# main.net
KiCad netlist of a schematic drawn in Altium Designer
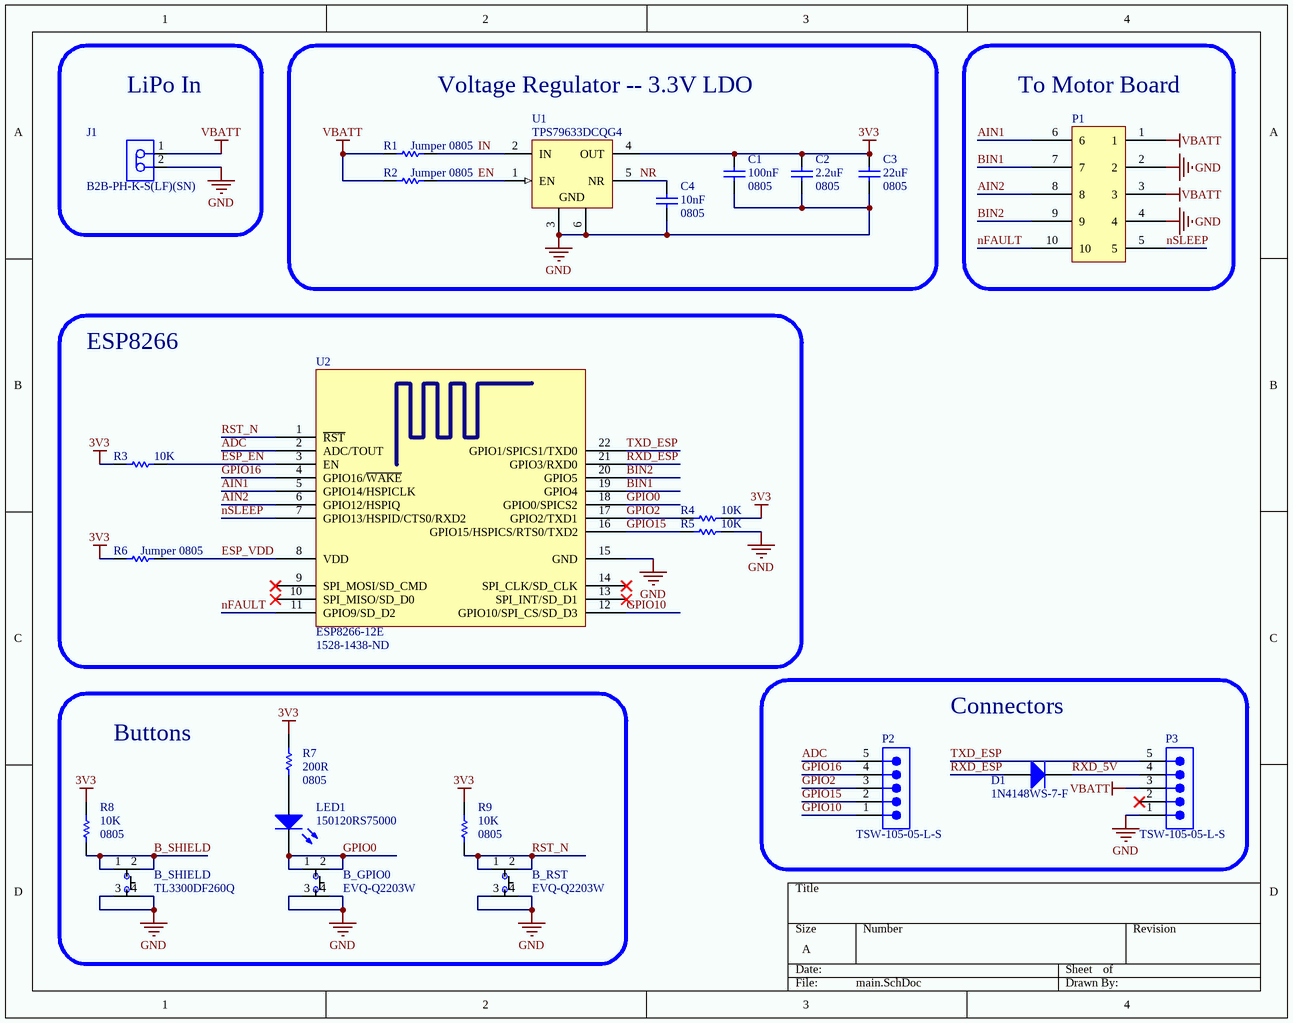
[diagram p0: main.SchDoc]

(export (version "E")
  (design (tool "Eeschema 10.0.6"))
  (components
    (comp (ref "B_GPIO0")
      (value "EVQ-Q2203W")
      (footprint "EVQ-Q2203W")
      (description "SWITCH TACTILE SPST-NO 0.02A 15V")
      (fields (field (name "MANUFACTURER") "Panasonic Electronic Components"))
      (libsource (lib "ESE292-2017F-Teaching-Staff") (part "EVQ-Q2203W"))
    )
    (comp (ref "B_RST")
      (value "EVQ-Q2203W")
      (footprint "EVQ-Q2203W")
      (description "SWITCH TACTILE SPST-NO 0.02A 15V")
      (fields (field (name "MANUFACTURER") "Panasonic Electronic Components"))
      (libsource (lib "ESE292-2017F-Teaching-Staff") (part "EVQ-Q2203W"))
    )
    (comp (ref "B_SHIELD")
      (value "TL3300DF260Q")
      (footprint "TL3300DF260Q")
      (description "SWITCH TACTILE SPST-NO 0.05A 12V")
      (fields (field (name "MANUFACTURER") "E-Switch"))
      (libsource (lib "ESE292-2017F-Teaching-Staff") (part "TL3300DF260Q"))
    )
    (comp (ref "C1")
      (value "100nF")
      (footprint "CAPC0805(2012)100_M")
      (description "CAP 100nF 10V ±20% 0805 (2012 Metric) Thickness 1mm SMD")
      (fields (field (name "TOLERANCE") "Â±20%") (field (name "CASE-EIA") "0805"))
      (libsource (lib "Altium Content Vault") (part "CMP-1036-04396-1"))
    )
    (comp (ref "C2")
      (value "2.2uF")
      (footprint "CAPC0805(2012)145_L")
      (description "CAP 2.2uF 10V ±20% 0805 (2012 Metric) Thickness 1.45mm SMD")
      (fields (field (name "CASE-EIA") "0805") (field (name "TOLERANCE") "Â±20%"))
      (libsource (lib "Altium Content Vault") (part "CMP-1036-04826-1"))
    )
    (comp (ref "C3")
      (value "22uF")
      (footprint "CAPC0805(2012)145_L")
      (description "CAP 22uF 10V ±10% 0805 (2012 Metric) Thickness 1.45mm SMD")
      (fields (field (name "CASE-EIA") "0805") (field (name "TOLERANCE") "Â±10%"))
      (libsource (lib "Altium Content Vault") (part "CMP-1036-04942-1"))
    )
    (comp (ref "C4")
      (value "10nF")
      (footprint "CAPC0805(2012)145_M")
      (description "CAP 10nF 10V ±10% 0805 (2012 Metric) Thickness 1.45mm SMD")
      (fields (field (name "CASE-EIA") "0805") (field (name "TOLERANCE") "Â±10%"))
      (libsource (lib "Altium Content Vault") (part "CMP-1036-03808-1"))
    )
    (comp (ref "D1")
      (value "1N4148WS-7-F")
      (footprint "DIOD-SOD323-2-A_V")
      (description "Fast Switching Diode, 75 V, 0.3 A, -65 to 150 degC, 2-Pin SOD323, RoHS, Tape and Reel")
      (libsource (lib "Altium Content Vault") (part "D-AK-2"))
    )
    (comp (ref "J1")
      (value "B2B-PH-K-S(LF)(SN)")
      (footprint "JST-B2B-PH-K-S_V")
      (fields (field (name "MANUFACTURER") "JST"))
      (libsource (lib "Altium Content Vault") (part "CN-2P-F-QF2"))
    )
    (comp (ref "LED1")
      (value "150120RS75000")
      (footprint "1206_A")
      (description "SMD mono-color Chip LED, WL-SMCW, Red")
      (fields (field (name "MANUFACTURER") "Wuerth Elektronik"))
      (libsource (lib "Altium Content Vault") (part "WE-LED_K1A2-2"))
    )
    (comp (ref "P1")
      (value "302-S101")
      (footprint "302-S101")
      (description "10 Positions Header, Shrouded Connector 0.100\" (2.54mm) Through Hole Gold")
      (fields (field (name "MANUFACTURER") "On-Shore Technology"))
      (libsource (lib "ESE292-2017F-Teaching-Staff") (part "302-S101"))
    )
    (comp (ref "P2")
      (value "TSW-105-05-L-S")
      (footprint "SMTC-TSW-105-05-X-S")
      (fields (field (name "MANUFACTURER") "Samtec"))
      (libsource (lib "Altium Content Vault") (part "SMTC-TSW-105-05-X-S"))
    )
    (comp (ref "P3")
      (value "TSW-105-05-L-S")
      (footprint "SMTC-TSW-105-05-X-S")
      (fields (field (name "MANUFACTURER") "Samtec"))
      (libsource (lib "Altium Content Vault") (part "SMTC-TSW-105-05-X-S"))
    )
    (comp (ref "R1")
      (value "Jumper 0805")
      (footprint "RESC0805(2012)_N")
      (description "Jumper 0805 (2012 Metric)")
      (fields (field (name "TOLERANCE") "None"))
      (libsource (lib "Altium Content Vault") (part "RES"))
    )
    (comp (ref "R2")
      (value "Jumper 0805")
      (footprint "RESC0805(2012)_N")
      (description "Jumper 0805 (2012 Metric)")
      (fields (field (name "TOLERANCE") "None"))
      (libsource (lib "Altium Content Vault") (part "RES"))
    )
    (comp (ref "R3")
      (value "10K")
      (footprint "RESC0805(2012)_L")
      (description "10K 0.125W 5% 0805 (2012 Metric)  SMD")
      (fields (field (name "POWER") "0.125 W") (field (name "TOLERANCE") "5 %"))
      (libsource (lib "Altium Content Vault") (part "CMP-1013-00098-1"))
    )
    (comp (ref "R4")
      (value "10K")
      (footprint "RESC0805(2012)_L")
      (description "10K 0.125W 5% 0805 (2012 Metric)  SMD")
      (fields (field (name "POWER") "0.125 W") (field (name "TOLERANCE") "5 %"))
      (libsource (lib "Altium Content Vault") (part "CMP-1013-00098-1"))
    )
    (comp (ref "R5")
      (value "10K")
      (footprint "RESC0805(2012)_L")
      (description "10K 0.125W 5% 0805 (2012 Metric)  SMD")
      (fields (field (name "POWER") "0.125 W") (field (name "TOLERANCE") "5 %"))
      (libsource (lib "Altium Content Vault") (part "CMP-1013-00098-1"))
    )
    (comp (ref "R6")
      (value "Jumper 0805")
      (footprint "RESC0805(2012)_N")
      (description "Jumper 0805 (2012 Metric)")
      (fields (field (name "TOLERANCE") "None"))
      (libsource (lib "Altium Content Vault") (part "RES"))
    )
    (comp (ref "R7")
      (value "200R")
      (footprint "RESC0805(2012)_N")
      (description "200R 0.125W 5% 0805 (2012 Metric)  SMD")
      (fields
        (field (name "TOLERANCE") "5 %")
        (field (name "CASE-EIA") "0805")
        (field (name "POWER") "0.125 W")
      )
      (libsource (lib "Altium Content Vault") (part "CMP-1013-00057-1"))
    )
    (comp (ref "R8")
      (value "10K")
      (footprint "RESC0805(2012)_L")
      (description "10K 0.125W 5% 0805 (2012 Metric)  SMD")
      (fields
        (field (name "CASE-EIA") "0805")
        (field (name "POWER") "0.125 W")
        (field (name "TOLERANCE") "5 %")
      )
      (libsource (lib "Altium Content Vault") (part "CMP-1013-00098-1"))
    )
    (comp (ref "R9")
      (value "10K")
      (footprint "RESC0805(2012)_L")
      (description "10K 0.125W 5% 0805 (2012 Metric)  SMD")
      (fields
        (field (name "CASE-EIA") "0805")
        (field (name "POWER") "0.125 W")
        (field (name "TOLERANCE") "5 %")
      )
      (libsource (lib "Altium Content Vault") (part "CMP-1013-00098-1"))
    )
    (comp (ref "U1")
      (value "TPS79633DCQG4")
      (footprint "DCQ0006A_L")
      (fields (field (name "MANUFACTURER") "Texas Instruments"))
      (libsource (lib "Altium Content Vault") (part "TI-TPS7XXXXXXXX"))
    )
    (comp (ref "U2")
      (value "ESP8266-12E")
      (footprint "ESP8266-12E")
      (fields
        (field (name "MANUFACTURER") "Adafruit Industries")
        (field (name "MANUFACTURER PART NUMBER") "2491")
        (field (name "SUPPLIER PART NUMBER 1") "1528-1438-ND")
      )
      (libsource (lib "ESE292-2017F-Teaching-Staff") (part "ESP8266-12E"))
    )
  )
  (nets
    (net (code "1") (name "/ADC") (class "Default")
      (node (ref "P2") (pin "5") (pinfunction "5_5") (pintype "passive"))
      (node (ref "U2") (pin "2") (pinfunction "ADC/TOUT_2") (pintype "passive"))
    )
    (net (code "2") (name "/AIN1") (class "Default")
      (node (ref "P1") (pin "6") (pinfunction "6_6") (pintype "passive"))
      (node (ref "U2") (pin "5") (pinfunction "GPIO14/HSPICLK_5") (pintype "passive"))
    )
    (net (code "3") (name "/AIN2") (class "Default")
      (node (ref "P1") (pin "8") (pinfunction "8_8") (pintype "passive"))
      (node (ref "U2") (pin "6") (pinfunction "GPIO12/HSPIQ_6") (pintype "passive"))
    )
    (net (code "4") (name "/BIN1") (class "Default")
      (node (ref "P1") (pin "7") (pinfunction "7_7") (pintype "passive"))
      (node (ref "U2") (pin "19") (pinfunction "GPIO4_19") (pintype "passive"))
    )
    (net (code "5") (name "/BIN2") (class "Default")
      (node (ref "P1") (pin "9") (pinfunction "9_9") (pintype "passive"))
      (node (ref "U2") (pin "20") (pinfunction "GPIO5_20") (pintype "passive"))
    )
    (net (code "6") (name "/B_SHIELD") (class "Default")
      (node (ref "B_SHIELD") (pin "1") (pinfunction "1_1") (pintype "passive"))
      (node (ref "B_SHIELD") (pin "2") (pinfunction "2_2") (pintype "passive"))
      (node (ref "R8") (pin "1") (pinfunction "1_1") (pintype "passive"))
    )
    (net (code "7") (name "/EN") (class "Default")
      (node (ref "R2") (pin "1") (pinfunction "1_1") (pintype "passive"))
      (node (ref "U1") (pin "1") (pinfunction "EN_1") (pintype "input"))
    )
    (net (code "8") (name "/ESP_EN") (class "Default")
      (node (ref "R3") (pin "2") (pinfunction "2_2") (pintype "passive"))
      (node (ref "U2") (pin "3") (pinfunction "EN_3") (pintype "passive"))
    )
    (net (code "9") (name "/ESP_VDD") (class "Default")
      (node (ref "R6") (pin "1") (pinfunction "1_1") (pintype "passive"))
      (node (ref "U2") (pin "8") (pinfunction "VDD_8") (pintype "passive"))
    )
    (net (code "10") (name "/GPIO0") (class "Default")
      (node (ref "B_GPIO0") (pin "1") (pinfunction "1_1") (pintype "power_in"))
      (node (ref "B_GPIO0") (pin "2") (pinfunction "2_2") (pintype "power_in"))
      (node (ref "LED1") (pin "1") (pinfunction "K_1") (pintype "passive"))
      (node (ref "U2") (pin "18") (pinfunction "GPIO0/SPICS2_18") (pintype "passive"))
    )
    (net (code "11") (name "/GPIO2") (class "Default")
      (node (ref "P2") (pin "3") (pinfunction "3_3") (pintype "passive"))
      (node (ref "R4") (pin "1") (pinfunction "1_1") (pintype "passive"))
      (node (ref "U2") (pin "17") (pinfunction "GPIO2/TXD1_17") (pintype "passive"))
    )
    (net (code "12") (name "/GPIO10") (class "Default")
      (node (ref "P2") (pin "1") (pinfunction "1_1") (pintype "passive"))
      (node (ref "U2") (pin "12") (pinfunction "GPIO10/SPI_CS/SD_D3_12") (pintype "passive"))
    )
    (net (code "13") (name "/GPIO15") (class "Default")
      (node (ref "P2") (pin "2") (pinfunction "2_2") (pintype "passive"))
      (node (ref "R5") (pin "1") (pinfunction "1_1") (pintype "passive"))
      (node (ref "U2") (pin "16") (pinfunction "GPIO15/HSPICS/RTS0/TXD2_16") (pintype "passive"))
    )
    (net (code "14") (name "/GPIO16") (class "Default")
      (node (ref "P2") (pin "4") (pinfunction "4_4") (pintype "passive"))
      (node (ref "U2") (pin "4") (pinfunction "GPIO16/~{WAKE}_4") (pintype "passive"))
    )
    (net (code "15") (name "/IN") (class "Default")
      (node (ref "R1") (pin "1") (pinfunction "1_1") (pintype "passive"))
      (node (ref "U1") (pin "2") (pinfunction "IN_2") (pintype "power_in"))
    )
    (net (code "16") (name "/NR") (class "Default")
      (node (ref "C4") (pin "1") (pinfunction "1_1") (pintype "passive"))
      (node (ref "U1") (pin "5") (pinfunction "NR_5") (pintype "passive"))
    )
    (net (code "17") (name "/RST_N") (class "Default")
      (node (ref "B_RST") (pin "1") (pinfunction "1_1") (pintype "power_in"))
      (node (ref "B_RST") (pin "2") (pinfunction "2_2") (pintype "power_in"))
      (node (ref "R9") (pin "1") (pinfunction "1_1") (pintype "passive"))
      (node (ref "U2") (pin "1") (pinfunction "~{RST}_1") (pintype "passive"))
    )
    (net (code "18") (name "/RXD_5V") (class "Default")
      (node (ref "D1") (pin "2") (pinfunction "K_2") (pintype "passive"))
      (node (ref "P3") (pin "4") (pinfunction "4_4") (pintype "passive"))
    )
    (net (code "19") (name "/RXD_ESP") (class "Default")
      (node (ref "D1") (pin "1") (pinfunction "A_1") (pintype "passive"))
      (node (ref "U2") (pin "21") (pinfunction "GPIO3/RXD0_21") (pintype "passive"))
    )
    (net (code "20") (name "/TXD_ESP") (class "Default")
      (node (ref "P3") (pin "5") (pinfunction "5_5") (pintype "passive"))
      (node (ref "U2") (pin "22") (pinfunction "GPIO1/SPICS1/TXD0_22") (pintype "passive"))
    )
    (net (code "21") (name "/nFAULT") (class "Default")
      (node (ref "P1") (pin "10") (pinfunction "10_10") (pintype "passive"))
      (node (ref "U2") (pin "11") (pinfunction "GPIO9/SD_D2_11") (pintype "passive"))
    )
    (net (code "22") (name "/nSLEEP") (class "Default")
      (node (ref "P1") (pin "5") (pinfunction "5_5") (pintype "passive"))
      (node (ref "U2") (pin "7") (pinfunction "GPIO13/HSPID/CTS0/RXD2_7") (pintype "passive"))
    )
    (net (code "23") (name "3V3") (class "Default")
      (node (ref "C1") (pin "2") (pinfunction "2_2") (pintype "passive"))
      (node (ref "C2") (pin "2") (pinfunction "2_2") (pintype "passive"))
      (node (ref "C3") (pin "2") (pinfunction "2_2") (pintype "passive"))
      (node (ref "R3") (pin "1") (pinfunction "1_1") (pintype "passive"))
      (node (ref "R4") (pin "2") (pinfunction "2_2") (pintype "passive"))
      (node (ref "R6") (pin "2") (pinfunction "2_2") (pintype "passive"))
      (node (ref "R7") (pin "2") (pinfunction "2_2") (pintype "passive"))
      (node (ref "R8") (pin "2") (pinfunction "2_2") (pintype "passive"))
      (node (ref "R9") (pin "2") (pinfunction "2_2") (pintype "passive"))
      (node (ref "U1") (pin "4") (pinfunction "OUT_4") (pintype "power_in"))
    )
    (net (code "24") (name "GND") (class "Default")
      (node (ref "B_GPIO0") (pin "3") (pinfunction "3_3") (pintype "power_in"))
      (node (ref "B_GPIO0") (pin "4") (pinfunction "4_4") (pintype "power_in"))
      (node (ref "B_RST") (pin "3") (pinfunction "3_3") (pintype "power_in"))
      (node (ref "B_RST") (pin "4") (pinfunction "4_4") (pintype "power_in"))
      (node (ref "B_SHIELD") (pin "3") (pinfunction "3_3") (pintype "passive"))
      (node (ref "B_SHIELD") (pin "4") (pinfunction "4_4") (pintype "passive"))
      (node (ref "C1") (pin "1") (pinfunction "1_1") (pintype "passive"))
      (node (ref "C2") (pin "1") (pinfunction "1_1") (pintype "passive"))
      (node (ref "C3") (pin "1") (pinfunction "1_1") (pintype "passive"))
      (node (ref "C4") (pin "2") (pinfunction "2_2") (pintype "passive"))
      (node (ref "J1") (pin "2") (pinfunction "2_2") (pintype "passive"))
      (node (ref "P1") (pin "2") (pinfunction "2_2") (pintype "passive"))
      (node (ref "P1") (pin "4") (pinfunction "4_4") (pintype "passive"))
      (node (ref "P3") (pin "1") (pinfunction "1_1") (pintype "passive"))
      (node (ref "R5") (pin "2") (pinfunction "2_2") (pintype "passive"))
      (node (ref "U1") (pin "3") (pinfunction "GND_3") (pintype "power_in"))
      (node (ref "U1") (pin "6") (pinfunction "GND_6") (pintype "power_in"))
      (node (ref "U2") (pin "15") (pinfunction "GND_15") (pintype "passive"))
    )
    (net (code "25") (name "Net-(LED1-A)") (class "Default")
      (node (ref "LED1") (pin "2") (pinfunction "A_2") (pintype "passive"))
      (node (ref "R7") (pin "1") (pinfunction "1_1") (pintype "passive"))
    )
    (net (code "26") (name "VBATT") (class "Default")
      (node (ref "J1") (pin "1") (pinfunction "1_1") (pintype "passive"))
      (node (ref "P1") (pin "1") (pinfunction "1_1") (pintype "passive"))
      (node (ref "P1") (pin "3") (pinfunction "3_3") (pintype "passive"))
      (node (ref "P3") (pin "3") (pinfunction "3_3") (pintype "passive"))
      (node (ref "R1") (pin "2") (pinfunction "2_2") (pintype "passive"))
      (node (ref "R2") (pin "2") (pinfunction "2_2") (pintype "passive"))
    )
    (net (code "27") (name "unconnected-(P3-Pad2)") (class "Default")
      (node (ref "P3") (pin "2") (pinfunction "2_2") (pintype "passive+no_connect"))
    )
    (net (code "28") (name "unconnected-(U2-SPI_CLK{slash}SD_CLK-Pad14)") (class "Default")
      (node (ref "U2") (pin "14") (pinfunction "SPI_CLK/SD_CLK_14") (pintype "passive+no_connect"))
    )
    (net (code "29") (name "unconnected-(U2-SPI_INT{slash}SD_D1-Pad13)") (class "Default")
      (node (ref "U2") (pin "13") (pinfunction "SPI_INT/SD_D1_13") (pintype "passive+no_connect"))
    )
    (net (code "30") (name "unconnected-(U2-SPI_MISO{slash}SD_D0-Pad10)") (class "Default")
      (node (ref "U2") (pin "10") (pinfunction "SPI_MISO/SD_D0_10") (pintype "passive+no_connect"))
    )
    (net (code "31") (name "unconnected-(U2-SPI_MOSI{slash}SD_CMD-Pad9)") (class "Default")
      (node (ref "U2") (pin "9") (pinfunction "SPI_MOSI/SD_CMD_9") (pintype "passive+no_connect"))
    )
  )
)
